# driver_motor.net
KiCad netlist of a schematic drawn in EAGLE
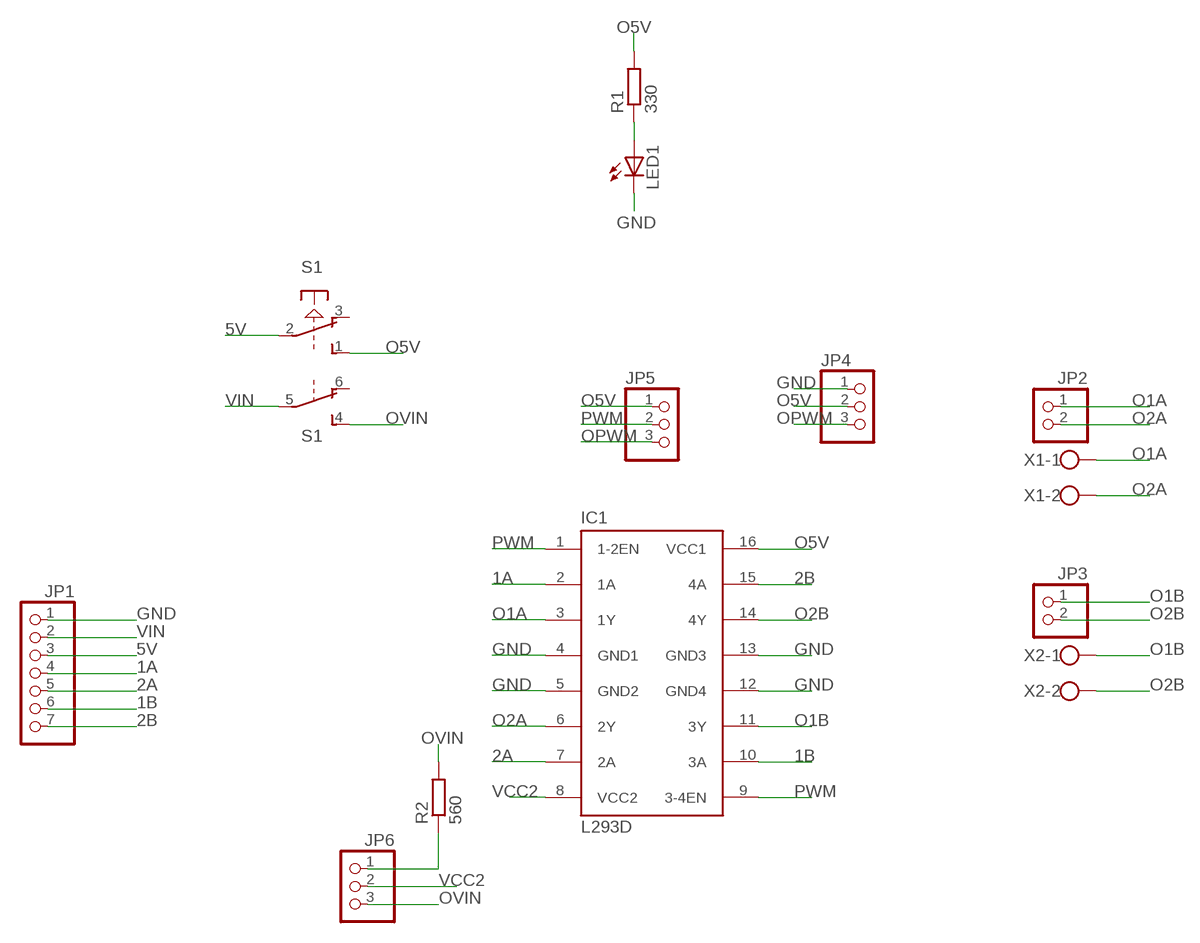
[diagram p0: schematic, sheet 1]

(export (version "E")
  (design (tool "Eeschema 10.0.6"))
  (components
    (comp (ref "IC1")
      (value "L293D")
      (footprint "eagle-import:DIL16")
      (libsource (lib "eagle-import") (part "L293D"))
    )
    (comp (ref "JP1")
      (value "PINHD-1X7")
      (footprint "eagle-import:1X07")
      (libsource (lib "eagle-import") (part "PINHD-1X7"))
    )
    (comp (ref "JP2")
      (value "PINHD-1X2")
      (footprint "eagle-import:1X02")
      (libsource (lib "eagle-import") (part "PINHD-1X2"))
    )
    (comp (ref "JP3")
      (value "PINHD-1X2")
      (footprint "eagle-import:1X02")
      (libsource (lib "eagle-import") (part "PINHD-1X2"))
    )
    (comp (ref "JP4")
      (value "PINHD-1X3")
      (footprint "eagle-import:1X03")
      (libsource (lib "eagle-import") (part "PINHD-1X3"))
    )
    (comp (ref "JP5")
      (value "PINHD-1X3")
      (footprint "eagle-import:1X03")
      (libsource (lib "eagle-import") (part "PINHD-1X3"))
    )
    (comp (ref "JP6")
      (value "PINHD-1X3")
      (footprint "eagle-import:1X03")
      (libsource (lib "eagle-import") (part "PINHD-1X3"))
    )
    (comp (ref "LED1")
      (value "LED3MM")
      (footprint "eagle-import:LED3MM")
      (libsource (lib "eagle-import") (part "LED3MM"))
    )
    (comp (ref "R1")
      (value "330")
      (footprint "eagle-import:0207_7")
      (libsource (lib "eagle-import") (part "R-EU_0207/7"))
    )
    (comp (ref "R2")
      (value "560")
      (footprint "eagle-import:0207_7")
      (libsource (lib "eagle-import") (part "R-EU_0207/7"))
    )
    (comp (ref "S1")
      (value "PVA2R")
      (footprint "eagle-import:PVA2R")
      (libsource (lib "eagle-import") (part "PVA2R"))
    )
    (comp (ref "X1")
      (value "W237-102")
      (footprint "eagle-import:W237-102")
      (fields (field (name "MPN") "237-102"))
      (libsource (lib "eagle-import") (part "W237-102"))
    )
    (comp (ref "X2")
      (value "W237-102")
      (footprint "eagle-import:W237-102")
      (fields (field (name "MPN") "237-102"))
      (libsource (lib "eagle-import") (part "W237-102"))
    )
  )
  (nets
    (net (code "1") (name "/1A") (class "Default")
      (node (ref "IC1") (pin "2") (pinfunction "1A_2") (pintype "input"))
      (node (ref "JP1") (pin "4") (pinfunction "4_4") (pintype "passive"))
    )
    (net (code "2") (name "/1B") (class "Default")
      (node (ref "IC1") (pin "10") (pinfunction "3A_10") (pintype "input"))
      (node (ref "JP1") (pin "6") (pinfunction "6_6") (pintype "passive"))
    )
    (net (code "3") (name "/2A") (class "Default")
      (node (ref "IC1") (pin "7") (pinfunction "2A_7") (pintype "input"))
      (node (ref "JP1") (pin "5") (pinfunction "5_5") (pintype "passive"))
    )
    (net (code "4") (name "/2B") (class "Default")
      (node (ref "IC1") (pin "15") (pinfunction "4A_15") (pintype "input"))
      (node (ref "JP1") (pin "7") (pinfunction "7_7") (pintype "passive"))
    )
    (net (code "5") (name "/5V") (class "Default")
      (node (ref "JP1") (pin "3") (pinfunction "3_3") (pintype "passive"))
      (node (ref "S1") (pin "2") (pinfunction "P_2") (pintype "passive"))
    )
    (net (code "6") (name "/GND") (class "Default")
      (node (ref "IC1") (pin "12") (pinfunction "GND4_12") (pintype "power_in"))
      (node (ref "IC1") (pin "13") (pinfunction "GND3_13") (pintype "power_in"))
      (node (ref "IC1") (pin "4") (pinfunction "GND1_4") (pintype "power_in"))
      (node (ref "IC1") (pin "5") (pinfunction "GND2_5") (pintype "power_in"))
      (node (ref "JP1") (pin "1") (pinfunction "1_1") (pintype "passive"))
      (node (ref "JP4") (pin "1") (pinfunction "1_1") (pintype "passive"))
      (node (ref "LED1") (pin "K") (pinfunction "C_K") (pintype "passive"))
    )
    (net (code "7") (name "/O1A") (class "Default")
      (node (ref "IC1") (pin "3") (pinfunction "1Y_3") (pintype "output"))
      (node (ref "JP2") (pin "1") (pinfunction "1_1") (pintype "passive"))
      (node (ref "X1") (pin "1") (pinfunction "KL_1") (pintype "passive"))
    )
    (net (code "8") (name "/O1B") (class "Default")
      (node (ref "IC1") (pin "11") (pinfunction "3Y_11") (pintype "output"))
      (node (ref "JP3") (pin "1") (pinfunction "1_1") (pintype "passive"))
      (node (ref "X2") (pin "1") (pinfunction "KL_1") (pintype "passive"))
    )
    (net (code "9") (name "/O2A") (class "Default")
      (node (ref "IC1") (pin "6") (pinfunction "2Y_6") (pintype "output"))
      (node (ref "JP2") (pin "2") (pinfunction "2_2") (pintype "passive"))
      (node (ref "X1") (pin "2") (pinfunction "KL_2") (pintype "passive"))
    )
    (net (code "10") (name "/O2B") (class "Default")
      (node (ref "IC1") (pin "14") (pinfunction "4Y_14") (pintype "output"))
      (node (ref "JP3") (pin "2") (pinfunction "2_2") (pintype "passive"))
      (node (ref "X2") (pin "2") (pinfunction "KL_2") (pintype "passive"))
    )
    (net (code "11") (name "/O5V") (class "Default")
      (node (ref "IC1") (pin "16") (pinfunction "VCC1_16") (pintype "power_in"))
      (node (ref "JP4") (pin "2") (pinfunction "2_2") (pintype "passive"))
      (node (ref "JP5") (pin "1") (pinfunction "1_1") (pintype "passive"))
      (node (ref "R1") (pin "2") (pinfunction "2_2") (pintype "passive"))
      (node (ref "S1") (pin "1") (pinfunction "S_1") (pintype "passive"))
    )
    (net (code "12") (name "/OPWM") (class "Default")
      (node (ref "JP4") (pin "3") (pinfunction "3_3") (pintype "passive"))
      (node (ref "JP5") (pin "3") (pinfunction "3_3") (pintype "passive"))
    )
    (net (code "13") (name "/OVIN") (class "Default")
      (node (ref "JP6") (pin "3") (pinfunction "3_3") (pintype "passive"))
      (node (ref "R2") (pin "2") (pinfunction "2_2") (pintype "passive"))
      (node (ref "S1") (pin "4") (pinfunction "S_4") (pintype "passive"))
    )
    (net (code "14") (name "/PWM") (class "Default")
      (node (ref "IC1") (pin "1") (pinfunction "1-2EN_1") (pintype "input"))
      (node (ref "IC1") (pin "9") (pinfunction "3-4EN_9") (pintype "input"))
      (node (ref "JP5") (pin "2") (pinfunction "2_2") (pintype "passive"))
    )
    (net (code "15") (name "/VCC2") (class "Default")
      (node (ref "IC1") (pin "8") (pinfunction "VCC2_8") (pintype "power_in"))
      (node (ref "JP6") (pin "2") (pinfunction "2_2") (pintype "passive"))
    )
    (net (code "16") (name "/VIN") (class "Default")
      (node (ref "JP1") (pin "2") (pinfunction "2_2") (pintype "passive"))
      (node (ref "S1") (pin "5") (pinfunction "P_5") (pintype "passive"))
    )
    (net (code "17") (name "Net-(JP6-Pad1)") (class "Default")
      (node (ref "JP6") (pin "1") (pinfunction "1_1") (pintype "passive"))
      (node (ref "R2") (pin "1") (pinfunction "1_1") (pintype "passive"))
    )
    (net (code "18") (name "Net-(LED1-PadA)") (class "Default")
      (node (ref "LED1") (pin "A") (pinfunction "A_A") (pintype "passive"))
      (node (ref "R1") (pin "1") (pinfunction "1_1") (pintype "passive"))
    )
    (net (code "19") (name "unconnected-(S1A-O-Pad3)") (class "Default")
      (node (ref "S1") (pin "3") (pinfunction "O_3") (pintype "passive"))
    )
    (net (code "20") (name "unconnected-(S1B-O-Pad6)") (class "Default")
      (node (ref "S1") (pin "6") (pinfunction "O_6") (pintype "passive"))
    )
  )
)
